# CH340E5T-R0.net
KiCad netlist of a schematic drawn in Altium Designer
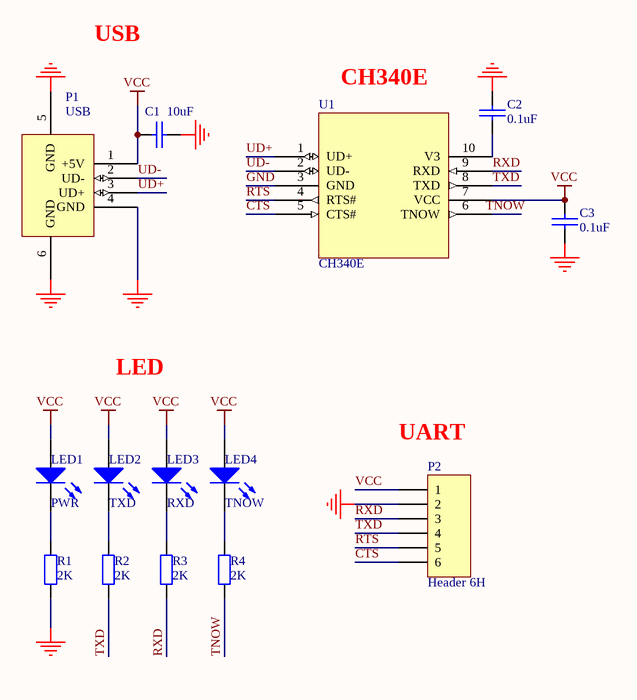
[diagram p0: CH340E5T-R0.SchDoc]

(export (version "E")
  (design (tool "Eeschema 10.0.6"))
  (components
    (comp (ref "C1")
      (value "10uF")
      (footprint "3216_C")
      (description "Capacitor")
      (libsource (lib "*") (part "CAP"))
    )
    (comp (ref "C2")
      (value "0.1uF")
      (footprint "0603_C")
      (description "Capacitor")
      (libsource (lib "*") (part "CAP"))
    )
    (comp (ref "C3")
      (value "0.1uF")
      (footprint "0603_C")
      (description "Capacitor")
      (libsource (lib "*") (part "CAP"))
    )
    (comp (ref "LED1")
      (value "PWR")
      (footprint "0603+")
      (description "Typical RED, GREEN, YELLOW, AMBER GaAs LED")
      (libsource (lib "*") (part "LED2"))
    )
    (comp (ref "LED2")
      (value "TXD")
      (footprint "0603+")
      (description "Typical RED, GREEN, YELLOW, AMBER GaAs LED")
      (libsource (lib "*") (part "LED2"))
    )
    (comp (ref "LED3")
      (value "RXD")
      (footprint "0603+")
      (description "Typical RED, GREEN, YELLOW, AMBER GaAs LED")
      (libsource (lib "*") (part "LED2"))
    )
    (comp (ref "LED4")
      (value "TNOW")
      (footprint "0603+")
      (description "Typical RED, GREEN, YELLOW, AMBER GaAs LED")
      (libsource (lib "*") (part "LED2"))
    )
    (comp (ref "P1") (value "USB") (footprint "USBAM") (libsource (lib "*") (part "USB")))
    (comp (ref "P2")
      (value "Header 6H")
      (footprint "SIP6-2.54mm")
      (description "Header, 6-Pin, Right Angle")
      (fields (field (name "PUBLISHER") "Altium Limited"))
      (libsource (lib "Miscellaneous Connectors") (part "Header 6H"))
    )
    (comp (ref "R1")
      (value "2K")
      (footprint "0603")
      (description "Resistor")
      (libsource (lib "*") (part "Res2"))
    )
    (comp (ref "R2")
      (value "2K")
      (footprint "0603")
      (description "Resistor")
      (libsource (lib "*") (part "Res2"))
    )
    (comp (ref "R3")
      (value "2K")
      (footprint "0603")
      (description "Resistor")
      (libsource (lib "*") (part "Res2"))
    )
    (comp (ref "R4")
      (value "2K")
      (footprint "0603")
      (description "Resistor")
      (libsource (lib "*") (part "Res2"))
    )
    (comp (ref "U1")
      (value "CH340E")
      (footprint "MSOP10")
      (description "USB to TTL Serial / UART")
      (libsource (lib "CHXXX") (part "CH340E"))
    )
  )
  (nets
    (net (code "1") (name "/CTS") (class "Default")
      (node (ref "P2") (pin "6") (pinfunction "6_6") (pintype "passive"))
      (node (ref "U1") (pin "5") (pinfunction "CTS#_5") (pintype "input"))
    )
    (net (code "2") (name "/RTS") (class "Default")
      (node (ref "P2") (pin "5") (pinfunction "5_5") (pintype "passive"))
      (node (ref "U1") (pin "4") (pinfunction "RTS#_4") (pintype "output"))
    )
    (net (code "3") (name "/RXD") (class "Default")
      (node (ref "P2") (pin "3") (pinfunction "3_3") (pintype "passive"))
      (node (ref "R3") (pin "2") (pinfunction "2_2") (pintype "passive"))
      (node (ref "U1") (pin "9") (pinfunction "RXD_9") (pintype "input"))
    )
    (net (code "4") (name "/TNOW") (class "Default")
      (node (ref "R4") (pin "2") (pinfunction "2_2") (pintype "passive"))
    )
    (net (code "5") (name "/TXD") (class "Default")
      (node (ref "P2") (pin "4") (pinfunction "4_4") (pintype "passive"))
      (node (ref "R2") (pin "2") (pinfunction "2_2") (pintype "passive"))
      (node (ref "U1") (pin "8") (pinfunction "TXD_8") (pintype "output"))
    )
    (net (code "6") (name "/UD+") (class "Default")
      (node (ref "P1") (pin "3") (pinfunction "UD+_3") (pintype "bidirectional"))
      (node (ref "U1") (pin "1") (pinfunction "UD+_1") (pintype "bidirectional"))
    )
    (net (code "7") (name "/UD-") (class "Default")
      (node (ref "P1") (pin "2") (pinfunction "UD-_2") (pintype "bidirectional"))
      (node (ref "U1") (pin "2") (pinfunction "UD-_2") (pintype "bidirectional"))
    )
    (net (code "8") (name "GND") (class "Default")
      (node (ref "C1") (pin "2") (pinfunction "2_2") (pintype "passive"))
      (node (ref "C2") (pin "2") (pinfunction "2_2") (pintype "passive"))
      (node (ref "C3") (pin "2") (pinfunction "2_2") (pintype "passive"))
      (node (ref "P1") (pin "4") (pinfunction "GND_4") (pintype "power_in"))
      (node (ref "P1") (pin "5") (pinfunction "GND_5") (pintype "power_in"))
      (node (ref "P1") (pin "6") (pinfunction "GND_6") (pintype "power_in"))
      (node (ref "P2") (pin "2") (pinfunction "2_2") (pintype "passive"))
      (node (ref "R1") (pin "2") (pinfunction "2_2") (pintype "passive"))
      (node (ref "U1") (pin "3") (pinfunction "GND_3") (pintype "power_in"))
    )
    (net (code "9") (name "Net-(LED1-K)") (class "Default")
      (node (ref "LED1") (pin "2") (pinfunction "K_2") (pintype "passive"))
      (node (ref "R1") (pin "1") (pinfunction "1_1") (pintype "passive"))
    )
    (net (code "10") (name "Net-(LED2-K)") (class "Default")
      (node (ref "LED2") (pin "2") (pinfunction "K_2") (pintype "passive"))
      (node (ref "R2") (pin "1") (pinfunction "1_1") (pintype "passive"))
    )
    (net (code "11") (name "Net-(LED3-K)") (class "Default")
      (node (ref "LED3") (pin "2") (pinfunction "K_2") (pintype "passive"))
      (node (ref "R3") (pin "1") (pinfunction "1_1") (pintype "passive"))
    )
    (net (code "12") (name "Net-(LED4-K)") (class "Default")
      (node (ref "LED4") (pin "2") (pinfunction "K_2") (pintype "passive"))
      (node (ref "R4") (pin "1") (pinfunction "1_1") (pintype "passive"))
    )
    (net (code "13") (name "Net-(U1-V3)") (class "Default")
      (node (ref "C2") (pin "1") (pinfunction "1_1") (pintype "passive"))
      (node (ref "U1") (pin "10") (pinfunction "V3_10") (pintype "power_in"))
    )
    (net (code "14") (name "VCC") (class "Default")
      (node (ref "C1") (pin "1") (pinfunction "1_1") (pintype "passive"))
      (node (ref "C3") (pin "1") (pinfunction "1_1") (pintype "passive"))
      (node (ref "LED1") (pin "1") (pinfunction "A_1") (pintype "passive"))
      (node (ref "LED2") (pin "1") (pinfunction "A_1") (pintype "passive"))
      (node (ref "LED3") (pin "1") (pinfunction "A_1") (pintype "passive"))
      (node (ref "LED4") (pin "1") (pinfunction "A_1") (pintype "passive"))
      (node (ref "P1") (pin "1") (pinfunction "+5V_1") (pintype "power_in"))
      (node (ref "P2") (pin "1") (pinfunction "1_1") (pintype "passive"))
      (node (ref "U1") (pin "7") (pinfunction "VCC_7") (pintype "power_in"))
    )
    (net (code "15") (name "unconnected-(U1-TNOW-Pad6)") (class "Default")
      (node (ref "U1") (pin "6") (pinfunction "TNOW_6") (pintype "output"))
    )
  )
)
